# dwm1000_optional.net
KiCad netlist of a schematic drawn in Altium Designer
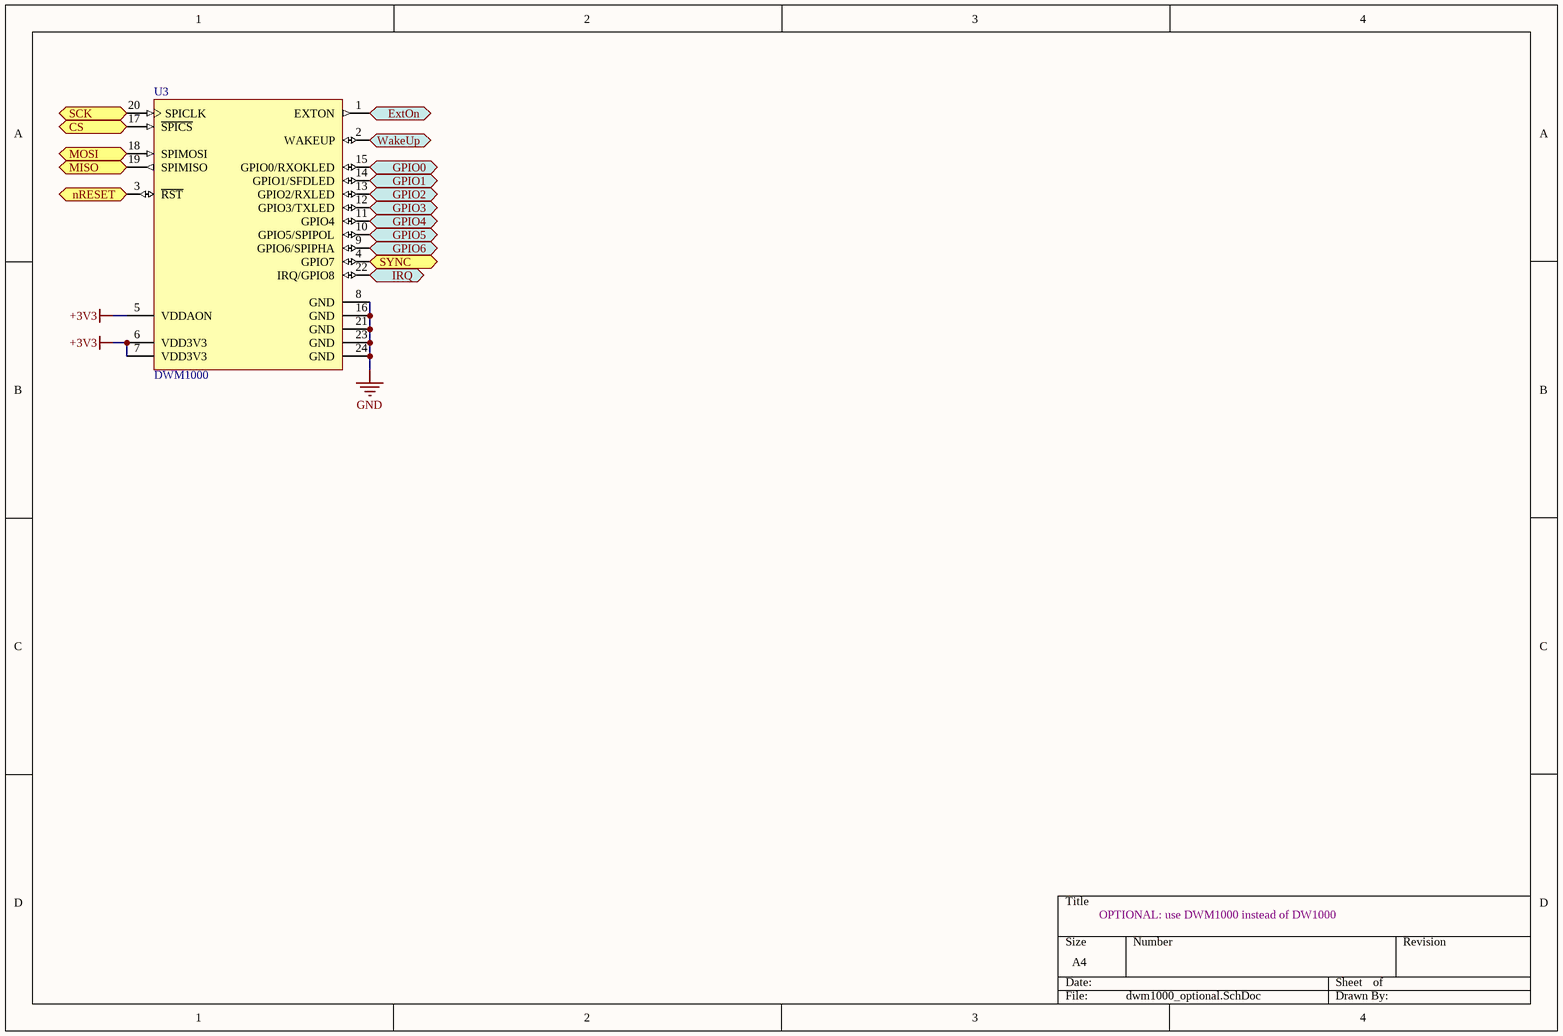
[diagram p0: dwm1000_optional.SchDoc]

(export (version "E")
  (design (tool "Eeschema 10.0.6"))
  (components
    (comp (ref "U3")
      (value "DWM1000")
      (footprint "DECW-DWM1000-24_V")
      (description "DW M1000 IEEE 802.15.4 -2011 UWB Transceiver Module")
      (fields (field (name "MANUFACTURER") "Decawave"))
      (libsource (lib "Altium Content Vault") (part "CMP-2000-05094-1"))
    )
  )
  (nets
    (net (code "1") (name "+3V3") (class "Default")
      (node (ref "U3") (pin "5") (pinfunction "VDDAON_5") (pintype "power_in"))
      (node (ref "U3") (pin "6") (pinfunction "VDD3V3_6") (pintype "power_in"))
      (node (ref "U3") (pin "7") (pinfunction "VDD3V3_7") (pintype "power_in"))
    )
    (net (code "2") (name "/CS") (class "Default")
      (node (ref "U3") (pin "17") (pinfunction "~{SPICS}_17") (pintype "input"))
    )
    (net (code "3") (name "/ExtOn") (class "Default")
      (node (ref "U3") (pin "1") (pinfunction "EXTON_1") (pintype "output"))
    )
    (net (code "4") (name "/GPIO0") (class "Default")
      (node (ref "U3") (pin "15") (pinfunction "GPIO0/RXOKLED_15") (pintype "bidirectional"))
    )
    (net (code "5") (name "/GPIO1") (class "Default")
      (node (ref "U3") (pin "14") (pinfunction "GPIO1/SFDLED_14") (pintype "bidirectional"))
    )
    (net (code "6") (name "/GPIO2") (class "Default")
      (node (ref "U3") (pin "13") (pinfunction "GPIO2/RXLED_13") (pintype "bidirectional"))
    )
    (net (code "7") (name "/GPIO3") (class "Default")
      (node (ref "U3") (pin "12") (pinfunction "GPIO3/TXLED_12") (pintype "bidirectional"))
    )
    (net (code "8") (name "/GPIO4") (class "Default")
      (node (ref "U3") (pin "11") (pinfunction "GPIO4_11") (pintype "bidirectional"))
    )
    (net (code "9") (name "/GPIO5") (class "Default")
      (node (ref "U3") (pin "10") (pinfunction "GPIO5/SPIPOL_10") (pintype "bidirectional"))
    )
    (net (code "10") (name "/GPIO6") (class "Default")
      (node (ref "U3") (pin "9") (pinfunction "GPIO6/SPIPHA_9") (pintype "bidirectional"))
    )
    (net (code "11") (name "/IRQ") (class "Default")
      (node (ref "U3") (pin "22") (pinfunction "IRQ/GPIO8_22") (pintype "bidirectional"))
    )
    (net (code "12") (name "/MISO") (class "Default")
      (node (ref "U3") (pin "19") (pinfunction "SPIMISO_19") (pintype "output"))
    )
    (net (code "13") (name "/MOSI") (class "Default")
      (node (ref "U3") (pin "18") (pinfunction "SPIMOSI_18") (pintype "input"))
    )
    (net (code "14") (name "/SCK") (class "Default")
      (node (ref "U3") (pin "20") (pinfunction "SPICLK_20") (pintype "input"))
    )
    (net (code "15") (name "/SYNC") (class "Default")
      (node (ref "U3") (pin "4") (pinfunction "GPIO7_4") (pintype "bidirectional"))
    )
    (net (code "16") (name "/WakeUp") (class "Default")
      (node (ref "U3") (pin "2") (pinfunction "WAKEUP_2") (pintype "bidirectional"))
    )
    (net (code "17") (name "/nRESET") (class "Default")
      (node (ref "U3") (pin "3") (pinfunction "~{RST}_3") (pintype "bidirectional"))
    )
    (net (code "18") (name "GND") (class "Default")
      (node (ref "U3") (pin "16") (pinfunction "GND_16") (pintype "power_in"))
      (node (ref "U3") (pin "21") (pinfunction "GND_21") (pintype "power_in"))
      (node (ref "U3") (pin "23") (pinfunction "GND_23") (pintype "power_in"))
      (node (ref "U3") (pin "24") (pinfunction "GND_24") (pintype "power_in"))
      (node (ref "U3") (pin "8") (pinfunction "GND_8") (pintype "power_in"))
    )
  )
)
